# MixBoard.net
KiCad netlist of a schematic drawn in Altium Designer
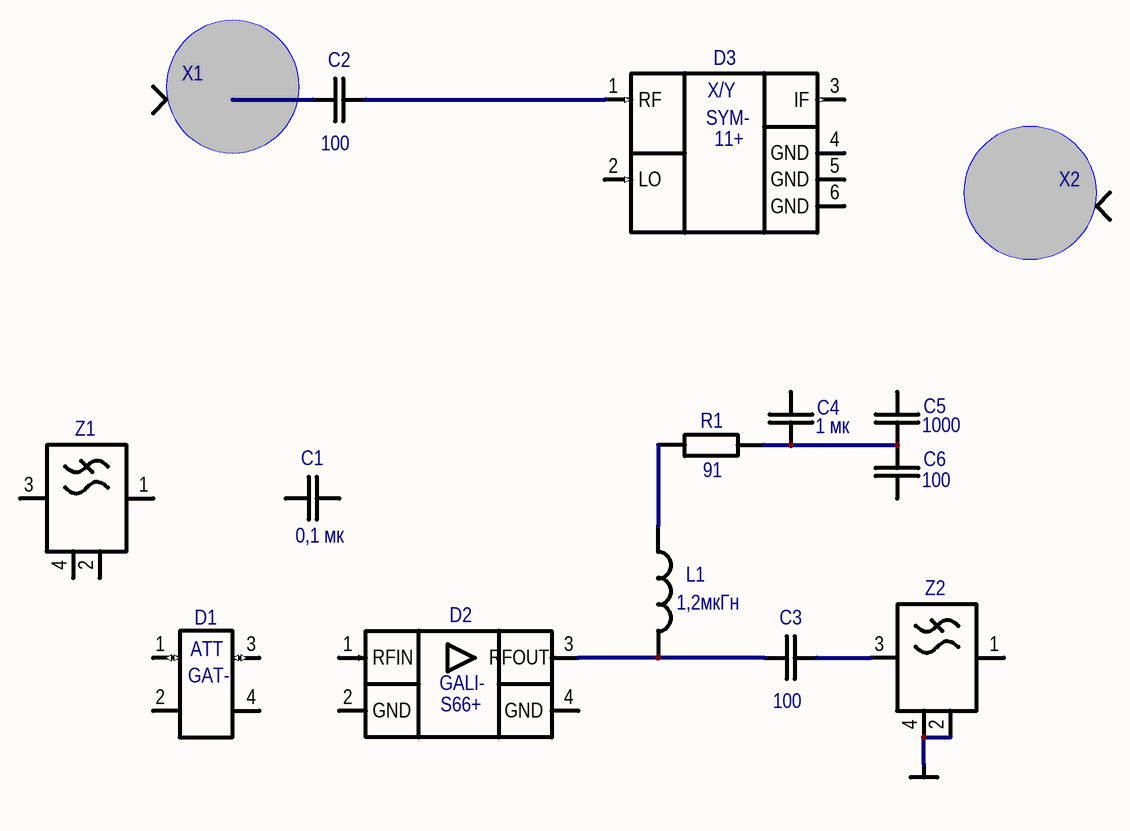
[diagram p0: MixBoard.SchDoc]

(export (version "E")
  (design (tool "Eeschema 10.0.6"))
  (components
    (comp (ref "*")
      (value "GND")
      (description "Корпус ЕСКД. Для \"наложения\" на штатный Power Bar")
      (libsource (lib "Other") (part "GND"))
    )
    (comp (ref "C1")
      (value "0,1 мк")
      (footprint "CAPC1608L")
      (description "Чип-конденсатор")
      (fields
        (field (name "TOLERANCE") "±10 %")
        (field (name "MANUFACTURERPARTNUMBER") "0603 X7R 0,1 мкФ ±10 % 50 В")
      )
      (libsource (lib "Passive") (part "C0603"))
    )
    (comp (ref "C2")
      (value "100")
      (footprint "CAPC1608L")
      (description "Чип-конденсатор")
      (fields
        (field (name "TOLERANCE") "±5 %")
        (field (name "MANUFACTURERPARTNUMBER") "0603 NP0 100 пФ ±5 % 50 В")
      )
      (libsource (lib "Passive") (part "C0603"))
    )
    (comp (ref "C3")
      (value "100")
      (footprint "CAPC1608L")
      (description "Чип-конденсатор")
      (fields
        (field (name "TOLERANCE") "±5 %")
        (field (name "MANUFACTURERPARTNUMBER") "0603 NP0 100 пФ ±5 % 50 В")
      )
      (libsource (lib "Passive") (part "C0603"))
    )
    (comp (ref "C4")
      (value "1 мк")
      (footprint "CAPC2012L")
      (description "Чип-конденсатор")
      (fields
        (field (name "TOLERANCE") "±10 %")
        (field (name "MANUFACTURERPARTNUMBER") "0805 X7R 1 мкФ ±10 % 50 В")
      )
      (libsource (lib "*") (part "C0805"))
    )
    (comp (ref "C5")
      (value "1000")
      (footprint "CAPC1608L")
      (description "Чип-конденсатор")
      (fields
        (field (name "TOLERANCE") "±5 %")
        (field (name "MANUFACTURERPARTNUMBER") "0603 NP0 1000 пФ ±5 % 50 В")
      )
      (libsource (lib "Passive") (part "C0603"))
    )
    (comp (ref "C6")
      (value "100")
      (footprint "CAPC1608L")
      (description "Чип-конденсатор")
      (fields
        (field (name "TOLERANCE") "±5 %")
        (field (name "MANUFACTURERPARTNUMBER") "0603 NP0 100 пФ ±5 % 50 В")
      )
      (libsource (lib "Passive") (part "C0603"))
    )
    (comp (ref "D1")
      (value "~")
      (footprint "MW_GAT-0")
      (description "Fixed attenuator DC-8000")
      (fields (field (name "MANUFACTURER") "Mini-Circuits") (field (name "MANUFACTURERPARTNUMBER") "GAT-10+"))
      (libsource (lib "Mini-Circuits") (part "GAT"))
    )
    (comp (ref "D2")
      (value "GALI-S66+")
      (footprint "SOT89-150P400X160-3N")
      (description "Monolithic Amplifier 50Ω      DC to 3 GHz")
      (fields (field (name "MANUFACTURER") "Mini-Circuits"))
      (libsource (lib "Mini-Circuits") (part "GALI-S66+"))
    )
    (comp (ref "D3")
      (value "SYM-11+")
      (footprint "MW_SYM-25DLHW")
      (description "Frequency Mixer 1 to 2500 MHz")
      (fields (field (name "MANUFACTURER") "Mini-Circuits"))
      (libsource (lib "Mini-Circuits") (part "SYM-11+"))
    )
    (comp (ref "L1")
      (value "1,2мкГн")
      (footprint "INDC4532L")
      (description "Индуктивность без магнитопровода")
      (fields (field (name "MANUFACTURER") "CoilCraft") (field (name "TOLERANCE") "±5 %"))
      (libsource (lib "Passive") (part "L1812"))
    )
    (comp (ref "R1")
      (value "91")
      (footprint "RESC2012L")
      (description "Чип-резистор")
      (fields (field (name "TOLERANCE") "±5 %") (field (name "MANUFACTURERPARTNUMBER") "0805 91 Ом ±5 %"))
      (libsource (lib "Any") (part "R0805"))
    )
    (comp (ref "X1")
      (value "22_SMA-50-0-15/111_NE")
      (footprint "TP0.8X1.5")
      (description "Розетка герметичная")
      (fields (field (name "MANUFACTURER") "HUBER+SUHNER"))
      (libsource (lib "") (part "22_SMA-50-0-15/111_NE_1"))
    )
    (comp (ref "X2")
      (value "22_SMA-50-0-15/111_NE")
      (footprint "TP0.8X1.5")
      (description "Розетка герметичная")
      (fields (field (name "MANUFACTURER") "HUBER+SUHNER"))
      (libsource (lib "Connectors") (part "22_SMA-50-0-15/111_NE"))
    )
    (comp (ref "Z1")
      (value "LFCN-95+")
      (footprint "FIL_3216x9.4")
      (description "Low Pass Filter")
      (fields (field (name "MANUFACTURER") "Mini-Circuits"))
      (libsource (lib "Passive") (part "LFCN"))
    )
    (comp (ref "Z2")
      (value "LFCN-95+")
      (footprint "FIL_3216x9.4")
      (description "Low Pass Filter")
      (fields (field (name "MANUFACTURER") "Mini-Circuits"))
      (libsource (lib "Passive") (part "LFCN"))
    )
  )
  (nets
    (net (code "1") (name "GND") (class "Default")
      (node (ref "Z2") (pin "2") (pinfunction "Ground_2") (pintype "power_in"))
      (node (ref "Z2") (pin "4") (pinfunction "Ground_4") (pintype "power_in"))
    )
    (net (code "2") (name "Net-(C2-Pad2)") (class "Default")
      (node (ref "C2") (pin "2") (pinfunction "2_2") (pintype "passive"))
      (node (ref "X1") (pin "1") (pinfunction "1_1") (pintype "passive"))
    )
    (net (code "3") (name "Net-(C4-Pad1)") (class "Default")
      (node (ref "C4") (pin "1") (pinfunction "1_1") (pintype "passive"))
      (node (ref "C5") (pin "1") (pinfunction "1_1") (pintype "passive"))
      (node (ref "C6") (pin "2") (pinfunction "2_2") (pintype "passive"))
      (node (ref "R1") (pin "1") (pinfunction "1_1") (pintype "passive"))
    )
    (net (code "4") (name "Net-(D2-RFOUT)") (class "Default")
      (node (ref "C3") (pin "2") (pinfunction "2_2") (pintype "passive"))
      (node (ref "D2") (pin "3") (pinfunction "RFOUT_3") (pintype "output"))
      (node (ref "L1") (pin "2") (pinfunction "2_2") (pintype "passive"))
    )
    (net (code "5") (name "Net-(D3-RF)") (class "Default")
      (node (ref "C2") (pin "1") (pinfunction "1_1") (pintype "passive"))
      (node (ref "D3") (pin "1") (pinfunction "RF_1") (pintype "input"))
    )
    (net (code "6") (name "Net-(L1-Pad1)") (class "Default")
      (node (ref "L1") (pin "1") (pinfunction "1_1") (pintype "passive"))
      (node (ref "R1") (pin "2") (pinfunction "2_2") (pintype "passive"))
    )
    (net (code "7") (name "Net-(Z2-Out)") (class "Default")
      (node (ref "C3") (pin "1") (pinfunction "1_1") (pintype "passive"))
      (node (ref "Z2") (pin "3") (pinfunction "Out_3") (pintype "passive"))
    )
    (net (code "8") (name "unconnected-(C1-Pad1)") (class "Default")
      (node (ref "C1") (pin "1") (pinfunction "1_1") (pintype "passive"))
    )
    (net (code "9") (name "unconnected-(C1-Pad2)") (class "Default")
      (node (ref "C1") (pin "2") (pinfunction "2_2") (pintype "passive"))
    )
    (net (code "10") (name "unconnected-(C4-Pad2)") (class "Default")
      (node (ref "C4") (pin "2") (pinfunction "2_2") (pintype "passive"))
    )
    (net (code "11") (name "unconnected-(C5-Pad2)") (class "Default")
      (node (ref "C5") (pin "2") (pinfunction "2_2") (pintype "passive"))
    )
    (net (code "12") (name "unconnected-(C6-Pad1)") (class "Default")
      (node (ref "C6") (pin "1") (pinfunction "1_1") (pintype "passive"))
    )
    (net (code "13") (name "unconnected-(D1-GND-Pad2)") (class "Default")
      (node (ref "D1") (pin "2") (pinfunction "GND_2") (pintype "power_in"))
    )
    (net (code "14") (name "unconnected-(D1-GND-Pad4)") (class "Default")
      (node (ref "D1") (pin "4") (pinfunction "GND_4") (pintype "power_in"))
    )
    (net (code "15") (name "unconnected-(D1-IN-Pad1)") (class "Default")
      (node (ref "D1") (pin "1") (pinfunction "IN_1") (pintype "bidirectional"))
    )
    (net (code "16") (name "unconnected-(D1-OUT-Pad3)") (class "Default")
      (node (ref "D1") (pin "3") (pinfunction "OUT_3") (pintype "bidirectional"))
    )
    (net (code "17") (name "unconnected-(D2-GND-Pad2)") (class "Default")
      (node (ref "D2") (pin "2") (pinfunction "GND_2") (pintype "power_in"))
    )
    (net (code "18") (name "unconnected-(D2-GND-Pad4)") (class "Default")
      (node (ref "D2") (pin "4") (pinfunction "GND_4") (pintype "power_in"))
    )
    (net (code "19") (name "unconnected-(D2-RFIN-Pad1)") (class "Default")
      (node (ref "D2") (pin "1") (pinfunction "RFIN_1") (pintype "input"))
    )
    (net (code "20") (name "unconnected-(D3-GND-Pad4)") (class "Default")
      (node (ref "D3") (pin "4") (pinfunction "GND_4") (pintype "power_in"))
    )
    (net (code "21") (name "unconnected-(D3-GND-Pad5)") (class "Default")
      (node (ref "D3") (pin "5") (pinfunction "GND_5") (pintype "power_in"))
    )
    (net (code "22") (name "unconnected-(D3-GND-Pad6)") (class "Default")
      (node (ref "D3") (pin "6") (pinfunction "GND_6") (pintype "power_in"))
    )
    (net (code "23") (name "unconnected-(D3-IF-Pad3)") (class "Default")
      (node (ref "D3") (pin "3") (pinfunction "IF_3") (pintype "output"))
    )
    (net (code "24") (name "unconnected-(D3-LO-Pad2)") (class "Default")
      (node (ref "D3") (pin "2") (pinfunction "LO_2") (pintype "input"))
    )
    (net (code "25") (name "unconnected-(X2-Pad1)") (class "Default")
      (node (ref "X2") (pin "1") (pinfunction "1_1") (pintype "passive"))
    )
    (net (code "26") (name "unconnected-(Z1-Ground-Pad2)") (class "Default")
      (node (ref "Z1") (pin "2") (pinfunction "Ground_2") (pintype "power_in"))
    )
    (net (code "27") (name "unconnected-(Z1-Ground-Pad4)") (class "Default")
      (node (ref "Z1") (pin "4") (pinfunction "Ground_4") (pintype "power_in"))
    )
    (net (code "28") (name "unconnected-(Z1-In-Pad1)") (class "Default")
      (node (ref "Z1") (pin "1") (pinfunction "In_1") (pintype "passive"))
    )
    (net (code "29") (name "unconnected-(Z1-Out-Pad3)") (class "Default")
      (node (ref "Z1") (pin "3") (pinfunction "Out_3") (pintype "passive"))
    )
    (net (code "30") (name "unconnected-(Z2-In-Pad1)") (class "Default")
      (node (ref "Z2") (pin "1") (pinfunction "In_1") (pintype "passive"))
    )
  )
)
